# LoRa.net
KiCad netlist of a schematic drawn in Altium Designer
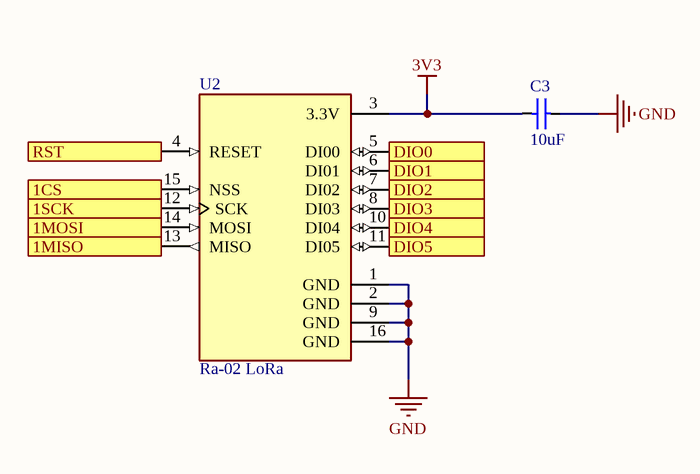
[diagram p0: LoRa.SchDoc]

(export (version "E")
  (design (tool "Eeschema 10.0.6"))
  (components
    (comp (ref "C3")
      (value "10uF")
      (footprint "CAP_0805")
      (description "Capacitor")
      (fields (field (name "PUBLISHER") "Altium Limited"))
      (libsource (lib "My Library") (part "CapSMD"))
    )
    (comp (ref "U2")
      (value "Ra-02 LoRa")
      (footprint "Ra-02")
      (description "LoRa Module Ra-02")
      (libsource (lib "Ven_lib") (part "Ra-02 LoRa"))
    )
  )
  (nets
    (net (code "1") (name "/1CS") (class "Default")
      (node (ref "U2") (pin "15") (pinfunction "NSS_15") (pintype "input"))
    )
    (net (code "2") (name "/1MISO") (class "Default")
      (node (ref "U2") (pin "13") (pinfunction "MISO_13") (pintype "output"))
    )
    (net (code "3") (name "/1MOSI") (class "Default")
      (node (ref "U2") (pin "14") (pinfunction "MOSI_14") (pintype "input"))
    )
    (net (code "4") (name "/1SCK") (class "Default")
      (node (ref "U2") (pin "12") (pinfunction "SCK_12") (pintype "input"))
    )
    (net (code "5") (name "/DIO0") (class "Default")
      (node (ref "U2") (pin "5") (pinfunction "DI00_5") (pintype "bidirectional"))
    )
    (net (code "6") (name "/DIO1") (class "Default")
      (node (ref "U2") (pin "6") (pinfunction "DI01_6") (pintype "bidirectional"))
    )
    (net (code "7") (name "/DIO2") (class "Default")
      (node (ref "U2") (pin "7") (pinfunction "DI02_7") (pintype "bidirectional"))
    )
    (net (code "8") (name "/DIO3") (class "Default")
      (node (ref "U2") (pin "8") (pinfunction "DI03_8") (pintype "bidirectional"))
    )
    (net (code "9") (name "/DIO4") (class "Default")
      (node (ref "U2") (pin "10") (pinfunction "DI04_10") (pintype "bidirectional"))
    )
    (net (code "10") (name "/DIO5") (class "Default")
      (node (ref "U2") (pin "11") (pinfunction "DI05_11") (pintype "bidirectional"))
    )
    (net (code "11") (name "/RST") (class "Default")
      (node (ref "U2") (pin "4") (pinfunction "RESET_4") (pintype "input"))
    )
    (net (code "12") (name "3V3") (class "Default")
      (node (ref "C3") (pin "2") (pinfunction "2_2") (pintype "passive"))
      (node (ref "U2") (pin "3") (pinfunction "3.3V_3") (pintype "power_in"))
    )
    (net (code "13") (name "GND") (class "Default")
      (node (ref "C3") (pin "1") (pinfunction "1_1") (pintype "passive"))
      (node (ref "U2") (pin "1") (pinfunction "GND_1") (pintype "power_in"))
      (node (ref "U2") (pin "16") (pinfunction "GND_16") (pintype "power_in"))
      (node (ref "U2") (pin "2") (pinfunction "GND_2") (pintype "power_in"))
      (node (ref "U2") (pin "9") (pinfunction "GND_9") (pintype "power_in"))
    )
  )
)
